# multi-pcb-cpu2.net
KiCad netlist of a schematic drawn in EAGLE
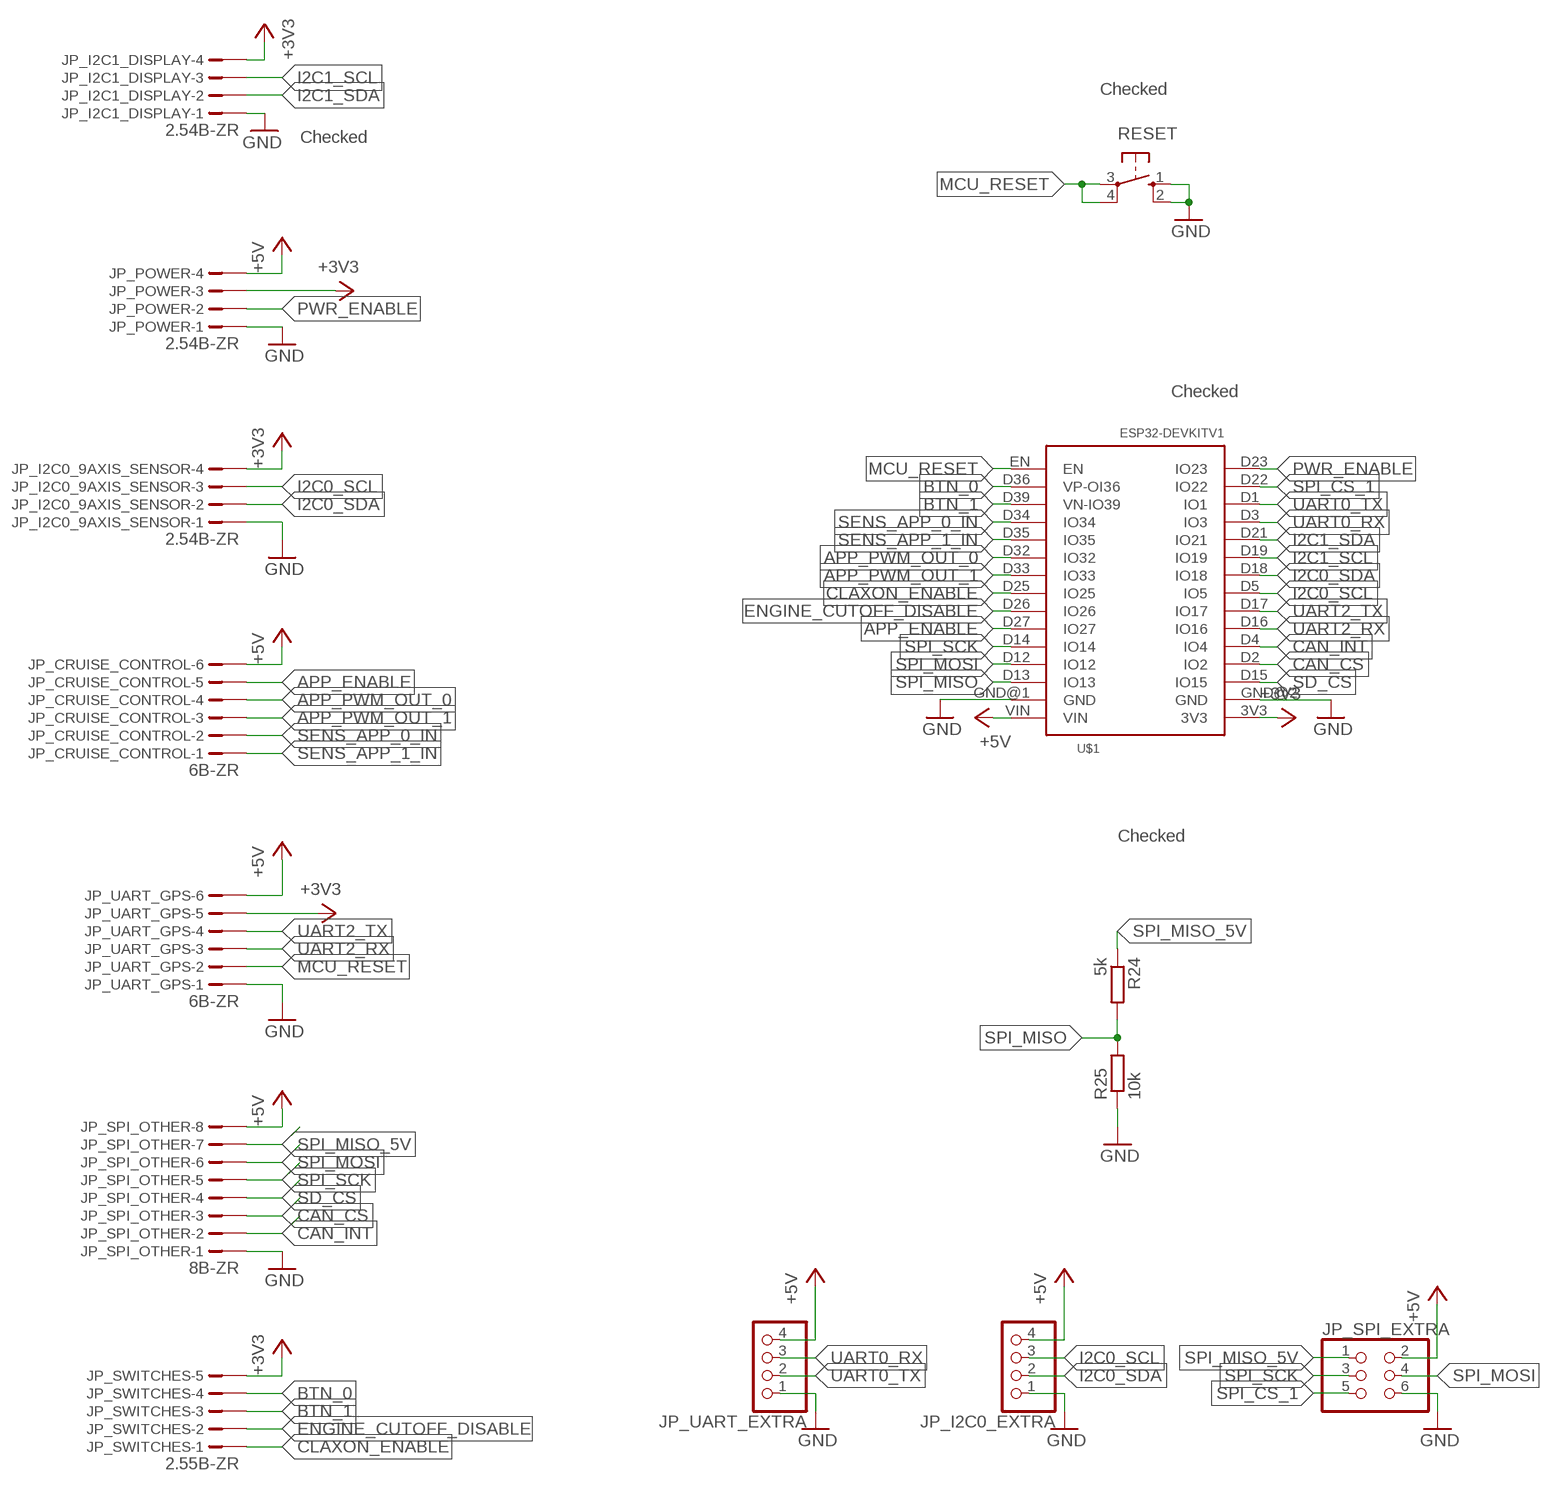
[diagram p0: schematic, sheet 1]

(export (version "E")
  (design (tool "Eeschema 10.0.6"))
  (components
    (comp (ref "JP_CRUISE_CONTROL")
      (value "6B-ZR")
      (footprint "eagle-import:B6B-ZR2.5")
      (libsource (lib "eagle-import") (part "?6B-ZR"))
    )
    (comp (ref "JP_I2C0_9AXIS_SENSOR")
      (value "2.54B-ZR")
      (footprint "eagle-import:B4B-ZR2.5")
      (libsource (lib "eagle-import") (part "?4B-ZR2.5"))
    )
    (comp (ref "JP_I2C0_EXTRA")
      (value "PINHD-1X4")
      (footprint "eagle-import:1X04")
      (libsource (lib "eagle-import") (part "PINHD-1X4"))
    )
    (comp (ref "JP_I2C1_DISPLAY")
      (value "2.54B-ZR")
      (footprint "eagle-import:B4B-ZR2.5")
      (libsource (lib "eagle-import") (part "?4B-ZR2.5"))
    )
    (comp (ref "JP_POWER")
      (value "2.54B-ZR")
      (footprint "eagle-import:B4B-ZR2.5")
      (libsource (lib "eagle-import") (part "?4B-ZR2.5"))
    )
    (comp (ref "JP_SPI_EXTRA")
      (value "PINHD-2X3")
      (footprint "eagle-import:2X03")
      (libsource (lib "eagle-import") (part "PINHD-2X3"))
    )
    (comp (ref "JP_SPI_OTHER")
      (value "8B-ZR")
      (footprint "eagle-import:B8B-ZR2.5")
      (libsource (lib "eagle-import") (part "?8B-ZR"))
    )
    (comp (ref "JP_SWITCHES")
      (value "2.55B-ZR")
      (footprint "eagle-import:B5B-ZR2.5")
      (libsource (lib "eagle-import") (part "?5B-ZR2.5"))
    )
    (comp (ref "JP_UART_EXTRA")
      (value "PINHD-1X4")
      (footprint "eagle-import:1X04")
      (libsource (lib "eagle-import") (part "PINHD-1X4"))
    )
    (comp (ref "JP_UART_GPS")
      (value "6B-ZR")
      (footprint "eagle-import:B6B-ZR2.5")
      (libsource (lib "eagle-import") (part "?6B-ZR"))
    )
    (comp (ref "R24")
      (value "5k")
      (footprint "eagle-import:0207_7")
      (libsource (lib "eagle-import") (part "R-EU_0207/7"))
    )
    (comp (ref "R25")
      (value "10k")
      (footprint "eagle-import:0207_7")
      (libsource (lib "eagle-import") (part "R-EU_0207/7"))
    )
    (comp (ref "RESET")
      (value "10-XX")
      (footprint "eagle-import:B3F-10XX")
      (fields (field (name "MPN") "B3F-1000"))
      (libsource (lib "eagle-import") (part "10-XX"))
    )
    (comp (ref "U$1")
      (value "ESP32DEVKITV1")
      (footprint "eagle-import:ESP32-DEVKITV1")
      (libsource (lib "eagle-import") (part "ESP32DEVKITV1"))
    )
  )
  (nets
    (net (code "1") (name "+3V3") (class "Default")
      (node (ref "JP_I2C0_9AXIS_SENSOR") (pin "4") (pinfunction "1_4") (pintype "passive"))
      (node (ref "JP_I2C1_DISPLAY") (pin "4") (pinfunction "1_4") (pintype "passive"))
      (node (ref "JP_POWER") (pin "3") (pinfunction "1_3") (pintype "passive"))
      (node (ref "JP_SWITCHES") (pin "5") (pinfunction "1_5") (pintype "passive"))
      (node (ref "JP_UART_GPS") (pin "5") (pinfunction "1_5") (pintype "passive"))
      (node (ref "U$1") (pin "3V3") (pinfunction "3V3_3V3") (pintype "bidirectional"))
    )
    (net (code "2") (name "+5V") (class "Default")
      (node (ref "JP_CRUISE_CONTROL") (pin "6") (pinfunction "1_6") (pintype "passive"))
      (node (ref "JP_I2C0_EXTRA") (pin "4") (pinfunction "4_4") (pintype "passive"))
      (node (ref "JP_POWER") (pin "4") (pinfunction "1_4") (pintype "passive"))
      (node (ref "JP_SPI_EXTRA") (pin "2") (pinfunction "2_2") (pintype "passive"))
      (node (ref "JP_SPI_OTHER") (pin "8") (pinfunction "1_8") (pintype "passive"))
      (node (ref "JP_UART_EXTRA") (pin "4") (pinfunction "4_4") (pintype "passive"))
      (node (ref "JP_UART_GPS") (pin "6") (pinfunction "1_6") (pintype "passive"))
      (node (ref "U$1") (pin "VIN") (pinfunction "VIN_VIN") (pintype "bidirectional"))
    )
    (net (code "3") (name "APP_ENABLE") (class "Default")
      (node (ref "JP_CRUISE_CONTROL") (pin "5") (pinfunction "1_5") (pintype "passive"))
      (node (ref "U$1") (pin "D27") (pinfunction "IO27_D27") (pintype "bidirectional"))
    )
    (net (code "4") (name "APP_PWM_OUT_0") (class "Default")
      (node (ref "JP_CRUISE_CONTROL") (pin "4") (pinfunction "1_4") (pintype "passive"))
      (node (ref "U$1") (pin "D32") (pinfunction "IO32_D32") (pintype "bidirectional"))
    )
    (net (code "5") (name "APP_PWM_OUT_1") (class "Default")
      (node (ref "JP_CRUISE_CONTROL") (pin "3") (pinfunction "1_3") (pintype "passive"))
      (node (ref "U$1") (pin "D33") (pinfunction "IO33_D33") (pintype "bidirectional"))
    )
    (net (code "6") (name "BTN_0") (class "Default")
      (node (ref "JP_SWITCHES") (pin "4") (pinfunction "1_4") (pintype "passive"))
      (node (ref "U$1") (pin "D36") (pinfunction "VP-OI36_D36") (pintype "bidirectional"))
    )
    (net (code "7") (name "BTN_1") (class "Default")
      (node (ref "JP_SWITCHES") (pin "3") (pinfunction "1_3") (pintype "passive"))
      (node (ref "U$1") (pin "D39") (pinfunction "VN-IO39_D39") (pintype "bidirectional"))
    )
    (net (code "8") (name "CAN_CS") (class "Default")
      (node (ref "JP_SPI_OTHER") (pin "3") (pinfunction "1_3") (pintype "passive"))
      (node (ref "U$1") (pin "D2") (pinfunction "IO2_D2") (pintype "bidirectional"))
    )
    (net (code "9") (name "CAN_INT") (class "Default")
      (node (ref "JP_SPI_OTHER") (pin "2") (pinfunction "1_2") (pintype "passive"))
      (node (ref "U$1") (pin "D4") (pinfunction "IO4_D4") (pintype "bidirectional"))
    )
    (net (code "10") (name "CLAXON_ENABLE") (class "Default")
      (node (ref "JP_SWITCHES") (pin "1") (pinfunction "1_1") (pintype "passive"))
      (node (ref "U$1") (pin "D25") (pinfunction "IO25_D25") (pintype "bidirectional"))
    )
    (net (code "11") (name "ENGINE_CUTOFF_DISABLE") (class "Default")
      (node (ref "JP_SWITCHES") (pin "2") (pinfunction "1_2") (pintype "passive"))
      (node (ref "U$1") (pin "D26") (pinfunction "IO26_D26") (pintype "bidirectional"))
    )
    (net (code "12") (name "GND") (class "Default")
      (node (ref "JP_I2C0_9AXIS_SENSOR") (pin "1") (pinfunction "1_1") (pintype "passive"))
      (node (ref "JP_I2C0_EXTRA") (pin "1") (pinfunction "1_1") (pintype "passive"))
      (node (ref "JP_I2C1_DISPLAY") (pin "1") (pinfunction "1_1") (pintype "passive"))
      (node (ref "JP_POWER") (pin "1") (pinfunction "1_1") (pintype "passive"))
      (node (ref "JP_SPI_EXTRA") (pin "6") (pinfunction "6_6") (pintype "passive"))
      (node (ref "JP_SPI_OTHER") (pin "1") (pinfunction "1_1") (pintype "passive"))
      (node (ref "JP_UART_EXTRA") (pin "1") (pinfunction "1_1") (pintype "passive"))
      (node (ref "JP_UART_GPS") (pin "1") (pinfunction "1_1") (pintype "passive"))
      (node (ref "R25") (pin "1") (pinfunction "1_1") (pintype "passive"))
      (node (ref "RESET") (pin "1") (pinfunction "S_1") (pintype "passive"))
      (node (ref "RESET") (pin "2") (pinfunction "S1_2") (pintype "passive"))
      (node (ref "U$1") (pin "GND@1") (pinfunction "GND_GND@1") (pintype "bidirectional"))
      (node (ref "U$1") (pin "GND@2") (pinfunction "GND_GND@2") (pintype "bidirectional"))
    )
    (net (code "13") (name "I2C0_SCL") (class "Default")
      (node (ref "JP_I2C0_9AXIS_SENSOR") (pin "3") (pinfunction "1_3") (pintype "passive"))
      (node (ref "JP_I2C0_EXTRA") (pin "3") (pinfunction "3_3") (pintype "passive"))
      (node (ref "U$1") (pin "D5") (pinfunction "IO5_D5") (pintype "bidirectional"))
    )
    (net (code "14") (name "I2C0_SDA") (class "Default")
      (node (ref "JP_I2C0_9AXIS_SENSOR") (pin "2") (pinfunction "1_2") (pintype "passive"))
      (node (ref "JP_I2C0_EXTRA") (pin "2") (pinfunction "2_2") (pintype "passive"))
      (node (ref "U$1") (pin "D18") (pinfunction "IO18_D18") (pintype "bidirectional"))
    )
    (net (code "15") (name "I2C1_SCL") (class "Default")
      (node (ref "JP_I2C1_DISPLAY") (pin "3") (pinfunction "1_3") (pintype "passive"))
      (node (ref "U$1") (pin "D19") (pinfunction "IO19_D19") (pintype "bidirectional"))
    )
    (net (code "16") (name "I2C1_SDA") (class "Default")
      (node (ref "JP_I2C1_DISPLAY") (pin "2") (pinfunction "1_2") (pintype "passive"))
      (node (ref "U$1") (pin "D21") (pinfunction "IO21_D21") (pintype "bidirectional"))
    )
    (net (code "17") (name "MCU_RESET") (class "Default")
      (node (ref "JP_UART_GPS") (pin "2") (pinfunction "1_2") (pintype "passive"))
      (node (ref "RESET") (pin "3") (pinfunction "P_3") (pintype "passive"))
      (node (ref "RESET") (pin "4") (pinfunction "P1_4") (pintype "passive"))
      (node (ref "U$1") (pin "EN") (pinfunction "EN_EN") (pintype "bidirectional"))
    )
    (net (code "18") (name "PWR_ENABLE") (class "Default")
      (node (ref "JP_POWER") (pin "2") (pinfunction "1_2") (pintype "passive"))
      (node (ref "U$1") (pin "D23") (pinfunction "IO23_D23") (pintype "bidirectional"))
    )
    (net (code "19") (name "SD_CS") (class "Default")
      (node (ref "JP_SPI_OTHER") (pin "4") (pinfunction "1_4") (pintype "passive"))
      (node (ref "U$1") (pin "D15") (pinfunction "IO15_D15") (pintype "bidirectional"))
    )
    (net (code "20") (name "SENS_APP_0_IN") (class "Default")
      (node (ref "JP_CRUISE_CONTROL") (pin "2") (pinfunction "1_2") (pintype "passive"))
      (node (ref "U$1") (pin "D34") (pinfunction "IO34_D34") (pintype "bidirectional"))
    )
    (net (code "21") (name "SENS_APP_1_IN") (class "Default")
      (node (ref "JP_CRUISE_CONTROL") (pin "1") (pinfunction "1_1") (pintype "passive"))
      (node (ref "U$1") (pin "D35") (pinfunction "IO35_D35") (pintype "bidirectional"))
    )
    (net (code "22") (name "SPI_CS_1") (class "Default")
      (node (ref "JP_SPI_EXTRA") (pin "5") (pinfunction "5_5") (pintype "passive"))
      (node (ref "U$1") (pin "D22") (pinfunction "IO22_D22") (pintype "bidirectional"))
    )
    (net (code "23") (name "SPI_MISO") (class "Default")
      (node (ref "R24") (pin "2") (pinfunction "2_2") (pintype "passive"))
      (node (ref "R25") (pin "2") (pinfunction "2_2") (pintype "passive"))
      (node (ref "U$1") (pin "D13") (pinfunction "IO13_D13") (pintype "bidirectional"))
    )
    (net (code "24") (name "SPI_MISO_5V") (class "Default")
      (node (ref "JP_SPI_EXTRA") (pin "1") (pinfunction "1_1") (pintype "passive"))
      (node (ref "JP_SPI_OTHER") (pin "7") (pinfunction "1_7") (pintype "passive"))
      (node (ref "R24") (pin "1") (pinfunction "1_1") (pintype "passive"))
    )
    (net (code "25") (name "SPI_MOSI") (class "Default")
      (node (ref "JP_SPI_EXTRA") (pin "4") (pinfunction "4_4") (pintype "passive"))
      (node (ref "JP_SPI_OTHER") (pin "6") (pinfunction "1_6") (pintype "passive"))
      (node (ref "U$1") (pin "D12") (pinfunction "IO12_D12") (pintype "bidirectional"))
    )
    (net (code "26") (name "SPI_SCK") (class "Default")
      (node (ref "JP_SPI_EXTRA") (pin "3") (pinfunction "3_3") (pintype "passive"))
      (node (ref "JP_SPI_OTHER") (pin "5") (pinfunction "1_5") (pintype "passive"))
      (node (ref "U$1") (pin "D14") (pinfunction "IO14_D14") (pintype "bidirectional"))
    )
    (net (code "27") (name "UART0_RX") (class "Default")
      (node (ref "JP_UART_EXTRA") (pin "3") (pinfunction "3_3") (pintype "passive"))
      (node (ref "U$1") (pin "D3") (pinfunction "IO3_D3") (pintype "bidirectional"))
    )
    (net (code "28") (name "UART0_TX") (class "Default")
      (node (ref "JP_UART_EXTRA") (pin "2") (pinfunction "2_2") (pintype "passive"))
      (node (ref "U$1") (pin "D1") (pinfunction "IO1_D1") (pintype "bidirectional"))
    )
    (net (code "29") (name "UART2_RX") (class "Default")
      (node (ref "JP_UART_GPS") (pin "3") (pinfunction "1_3") (pintype "passive"))
      (node (ref "U$1") (pin "D16") (pinfunction "IO16_D16") (pintype "bidirectional"))
    )
    (net (code "30") (name "UART2_TX") (class "Default")
      (node (ref "JP_UART_GPS") (pin "4") (pinfunction "1_4") (pintype "passive"))
      (node (ref "U$1") (pin "D17") (pinfunction "IO17_D17") (pintype "bidirectional"))
    )
  )
)
